# interface.net
KiCad netlist of a schematic drawn in Altium Designer
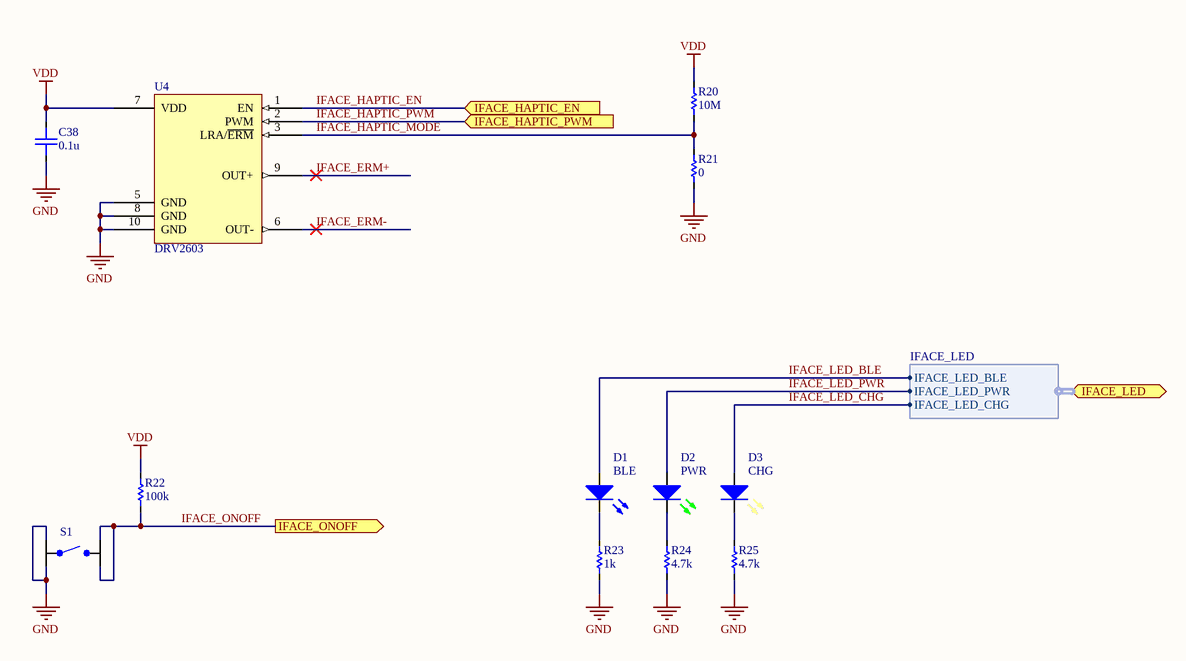
[diagram p0: interface.SchDoc]

(export (version "E")
  (design (tool "Eeschema 10.0.6"))
  (components
    (comp (ref "C38")
      (value "0.1u")
      (footprint "C0402")
      (description "Capacitor")
      (libsource (lib "misc") (part "Capacitor"))
    )
    (comp (ref "D1")
      (value "BLE")
      (footprint "WL-SMCW 0603")
      (description "LED - Blue, 3.2V, 0603")
      (libsource (lib "ecg-go") (part "150060BS75000"))
    )
    (comp (ref "D2")
      (value "PWR")
      (footprint "WL-SMCW 0603")
      (description "LED - Green, 2V, 0603")
      (libsource (lib "ecg-go") (part "150060VS75000"))
    )
    (comp (ref "D3")
      (value "CHG")
      (footprint "WL-SMCW 0603")
      (description "LED - Yellow, 2V, 0603")
      (libsource (lib "ecg-go") (part "150060YS75000"))
    )
    (comp (ref "R20")
      (value "10M")
      (footprint "R0402")
      (description "Resistor")
      (libsource (lib "misc") (part "Resistor"))
    )
    (comp (ref "R21")
      (value "0")
      (footprint "R0402")
      (description "Resistor")
      (libsource (lib "misc") (part "Resistor"))
    )
    (comp (ref "R22")
      (value "100k")
      (footprint "R0402")
      (description "Resistor")
      (libsource (lib "misc") (part "Resistor"))
    )
    (comp (ref "R23")
      (value "1k")
      (footprint "R0402")
      (description "Resistor")
      (libsource (lib "misc") (part "Resistor"))
    )
    (comp (ref "R24")
      (value "4.7k")
      (footprint "R0402")
      (description "Resistor")
      (libsource (lib "misc") (part "Resistor"))
    )
    (comp (ref "R25")
      (value "4.7k")
      (footprint "R0402")
      (description "Resistor")
      (libsource (lib "misc") (part "Resistor"))
    )
    (comp (ref "S1")
      (value "WE434351045816")
      (footprint "WE434351045816")
      (description "Switch - Tactile, Off-Mom, SPST, Side-Actuated")
      (libsource (lib "ecg-go") (part "WE434351045816"))
    )
    (comp (ref "U4")
      (value "DRV2603")
      (footprint "DRV2603")
      (description "IC - Haptic Drive, ERM/LRA, Auto Resonance")
      (libsource (lib "ecg-go") (part "DRV2603"))
    )
  )
  (nets
    (net (code "2") (name "/IFACE_ERM+") (class "Default")
      (node (ref "U4") (pin "9") (pinfunction "OUT+_9") (pintype "output"))
    )
    (net (code "3") (name "/IFACE_ERM-") (class "Default")
      (node (ref "U4") (pin "6") (pinfunction "OUT-_6") (pintype "output"))
    )
    (net (code "4") (name "/IFACE_HAPTIC_EN") (class "Default")
      (node (ref "U4") (pin "1") (pinfunction "EN_1") (pintype "input"))
    )
    (net (code "5") (name "/IFACE_HAPTIC_MODE") (class "Default")
      (node (ref "R20") (pin "1") (pinfunction "1_1") (pintype "passive"))
      (node (ref "R21") (pin "2") (pinfunction "2_2") (pintype "passive"))
      (node (ref "U4") (pin "3") (pinfunction "LRA/~{ERM}_3") (pintype "input"))
    )
    (net (code "6") (name "/IFACE_HAPTIC_PWM") (class "Default")
      (node (ref "U4") (pin "2") (pinfunction "PWM_2") (pintype "input"))
    )
    (net (code "7") (name "/IFACE_LED_BLE") (class "Default")
      (node (ref "D1") (pin "2") (pinfunction "A_2") (pintype "passive"))
    )
    (net (code "8") (name "/IFACE_LED_CHG") (class "Default")
      (node (ref "D3") (pin "2") (pinfunction "A_2") (pintype "passive"))
    )
    (net (code "9") (name "/IFACE_LED_PWR") (class "Default")
      (node (ref "D2") (pin "2") (pinfunction "A_2") (pintype "passive"))
    )
    (net (code "10") (name "/IFACE_ONOFF") (class "Default")
      (node (ref "R22") (pin "1") (pinfunction "1_1") (pintype "passive"))
      (node (ref "S1") (pin "2") (pinfunction "2_2") (pintype "passive"))
      (node (ref "S1") (pin "4") (pinfunction "4_4") (pintype "passive"))
    )
    (net (code "12") (name "GND") (class "Default")
      (node (ref "C38") (pin "1") (pinfunction "1_1") (pintype "passive"))
      (node (ref "R21") (pin "1") (pinfunction "1_1") (pintype "passive"))
      (node (ref "R23") (pin "1") (pinfunction "1_1") (pintype "passive"))
      (node (ref "R24") (pin "1") (pinfunction "1_1") (pintype "passive"))
      (node (ref "R25") (pin "1") (pinfunction "1_1") (pintype "passive"))
      (node (ref "S1") (pin "1") (pinfunction "1_1") (pintype "passive"))
      (node (ref "S1") (pin "3") (pinfunction "3_3") (pintype "passive"))
      (node (ref "U4") (pin "10") (pinfunction "GND_10") (pintype "power_in"))
      (node (ref "U4") (pin "5") (pinfunction "GND_5") (pintype "power_in"))
      (node (ref "U4") (pin "8") (pinfunction "GND_8") (pintype "power_in"))
    )
    (net (code "13") (name "Net-(D1-K)") (class "Default")
      (node (ref "D1") (pin "1") (pinfunction "K_1") (pintype "passive"))
      (node (ref "R23") (pin "2") (pinfunction "2_2") (pintype "passive"))
    )
    (net (code "14") (name "Net-(D2-K)") (class "Default")
      (node (ref "D2") (pin "1") (pinfunction "K_1") (pintype "passive"))
      (node (ref "R24") (pin "2") (pinfunction "2_2") (pintype "passive"))
    )
    (net (code "15") (name "Net-(D3-K)") (class "Default")
      (node (ref "D3") (pin "1") (pinfunction "K_1") (pintype "passive"))
      (node (ref "R25") (pin "2") (pinfunction "2_2") (pintype "passive"))
    )
    (net (code "16") (name "VDD") (class "Default")
      (node (ref "C38") (pin "2") (pinfunction "2_2") (pintype "passive"))
      (node (ref "R20") (pin "2") (pinfunction "2_2") (pintype "passive"))
      (node (ref "R22") (pin "2") (pinfunction "2_2") (pintype "passive"))
      (node (ref "U4") (pin "7") (pinfunction "VDD_7") (pintype "power_in"))
    )
  )
)
